# G772X.net
KiCad netlist of a schematic drawn in EAGLE
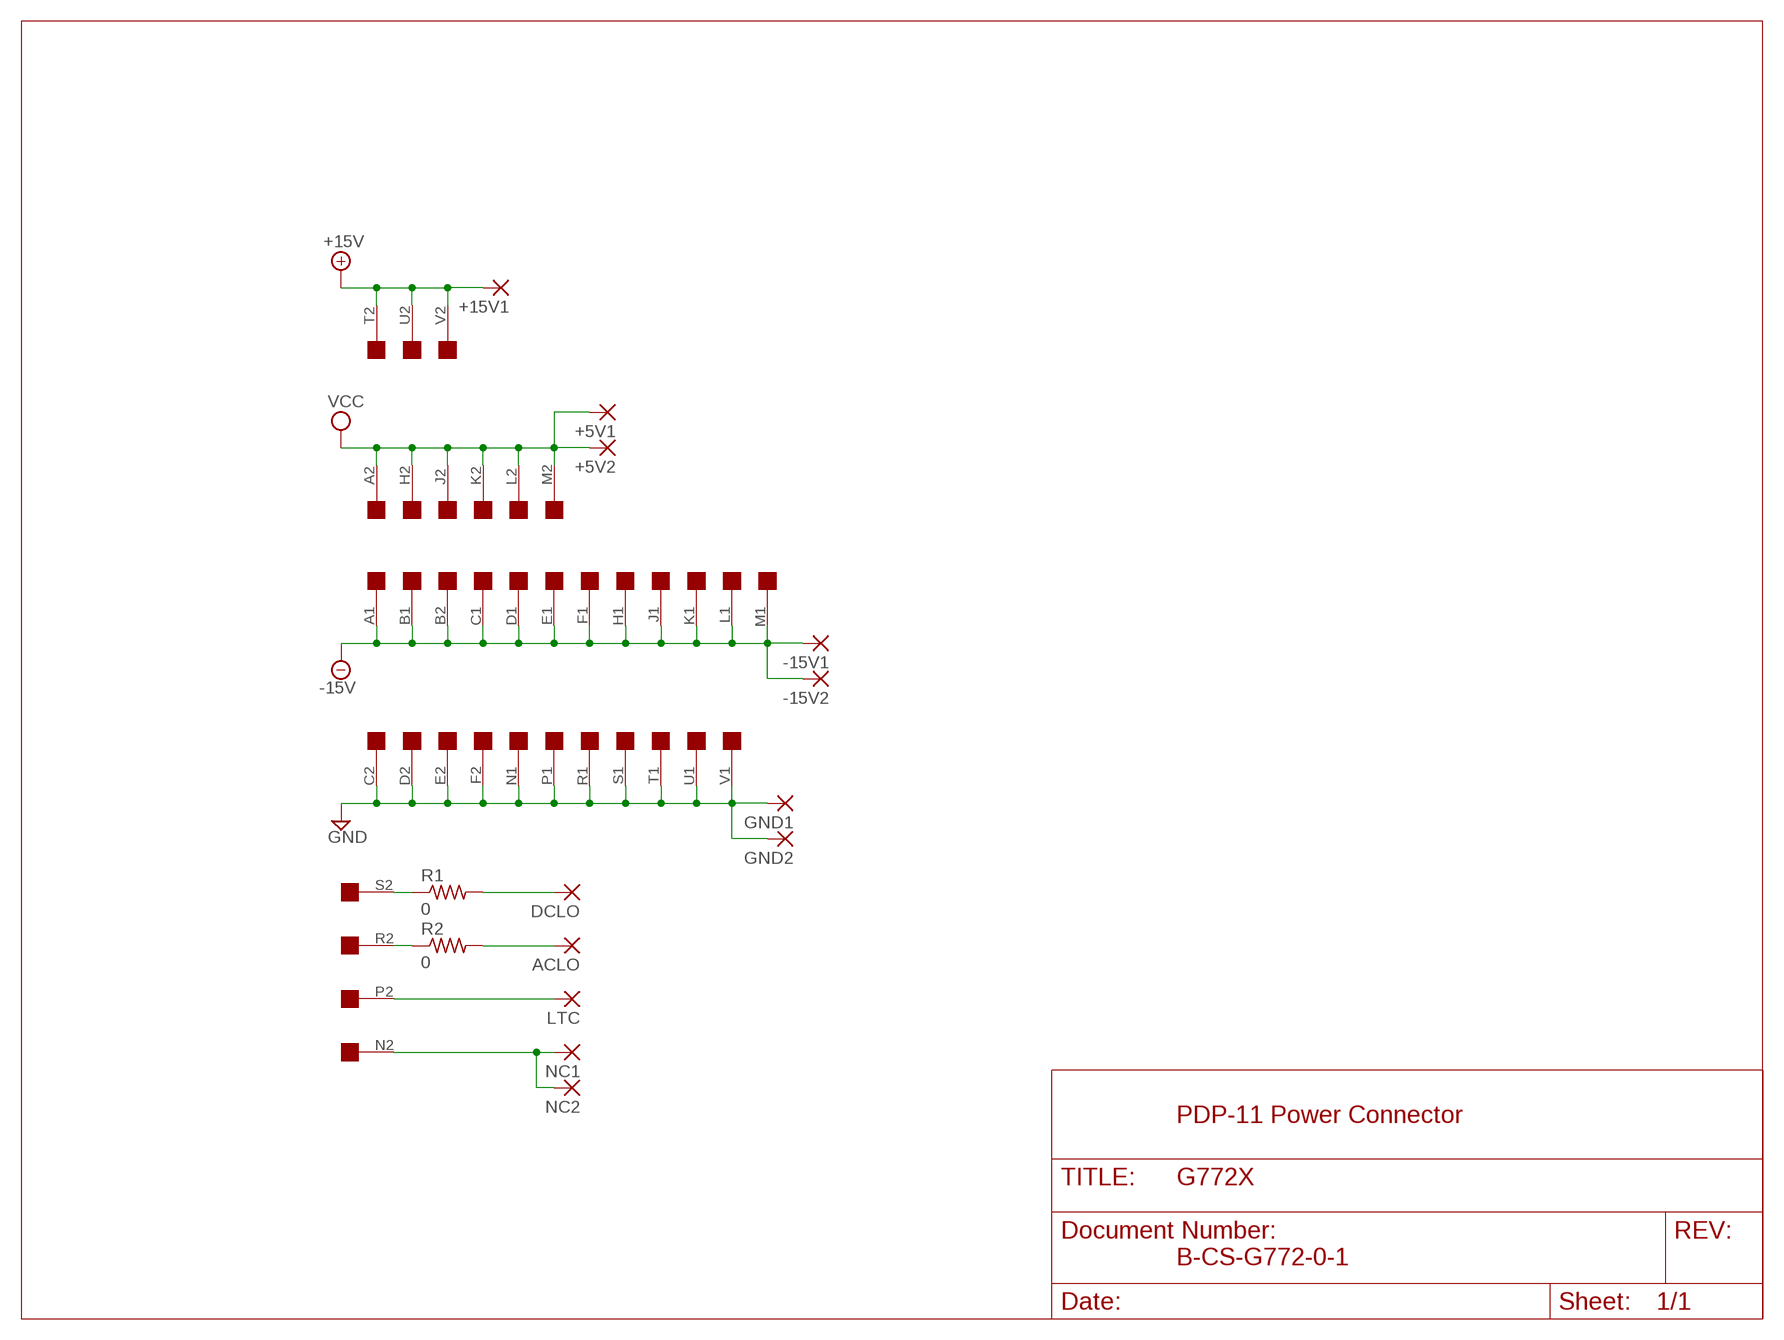
[diagram p0: schematic, sheet 1]

(export (version "E")
  (design (tool "Eeschema 10.0.6"))
  (components
    (comp (ref "+5V1")
      (value "2,54/1,0")
      (footprint "eagle-import:2,54_1,0")
      (libsource (lib "eagle-import") (part "2,54/1,0"))
    )
    (comp (ref "+5V2")
      (value "2,54/1,0")
      (footprint "eagle-import:2,54_1,0")
      (libsource (lib "eagle-import") (part "2,54/1,0"))
    )
    (comp (ref "+15V1")
      (value "2,54/1,0")
      (footprint "eagle-import:2,54_1,0")
      (libsource (lib "eagle-import") (part "2,54/1,0"))
    )
    (comp (ref "-15V1")
      (value "2,54/1,0")
      (footprint "eagle-import:2,54_1,0")
      (libsource (lib "eagle-import") (part "2,54/1,0"))
    )
    (comp (ref "-15V2")
      (value "2,54/1,0")
      (footprint "eagle-import:2,54_1,0")
      (libsource (lib "eagle-import") (part "2,54/1,0"))
    )
    (comp (ref "ACLO")
      (value "2,54/1,0")
      (footprint "eagle-import:2,54_1,0")
      (libsource (lib "eagle-import") (part "2,54/1,0"))
    )
    (comp (ref "DCLO")
      (value "2,54/1,0")
      (footprint "eagle-import:2,54_1,0")
      (libsource (lib "eagle-import") (part "2,54/1,0"))
    )
    (comp (ref "GND1")
      (value "2,54/1,0")
      (footprint "eagle-import:2,54_1,0")
      (libsource (lib "eagle-import") (part "2,54/1,0"))
    )
    (comp (ref "GND2")
      (value "2,54/1,0")
      (footprint "eagle-import:2,54_1,0")
      (libsource (lib "eagle-import") (part "2,54/1,0"))
    )
    (comp (ref "LTC")
      (value "2,54/1,0")
      (footprint "eagle-import:2,54_1,0")
      (libsource (lib "eagle-import") (part "2,54/1,0"))
    )
    (comp (ref "NC1")
      (value "2,54/1,0")
      (footprint "eagle-import:2,54_1,0")
      (libsource (lib "eagle-import") (part "2,54/1,0"))
    )
    (comp (ref "NC2")
      (value "2,54/1,0")
      (footprint "eagle-import:2,54_1,0")
      (libsource (lib "eagle-import") (part "2,54/1,0"))
    )
    (comp (ref "R1")
      (value "0")
      (footprint "eagle-import:0207_10")
      (libsource (lib "eagle-import") (part "R-US_0207/10"))
    )
    (comp (ref "R2")
      (value "0")
      (footprint "eagle-import:0207_10")
      (libsource (lib "eagle-import") (part "R-US_0207/10"))
    )
    (comp (ref "U$1")
      (value "SINGLE")
      (footprint "eagle-import:EDGE-CON2")
      (libsource (lib "eagle-import") (part "SINGLE"))
    )
  )
  (nets
    (net (code "1") (name "+15V") (class "Default")
      (node (ref "+15V1") (pin "1") (pinfunction "P_1") (pintype "passive"))
      (node (ref "U$1") (pin "T2") (pinfunction "1_T2") (pintype "bidirectional"))
      (node (ref "U$1") (pin "U2") (pinfunction "1_U2") (pintype "bidirectional"))
      (node (ref "U$1") (pin "V2") (pinfunction "1_V2") (pintype "bidirectional"))
    )
    (net (code "2") (name "-15V") (class "Default")
      (node (ref "-15V1") (pin "1") (pinfunction "P_1") (pintype "passive"))
      (node (ref "-15V2") (pin "1") (pinfunction "P_1") (pintype "passive"))
      (node (ref "U$1") (pin "A1") (pinfunction "1_A1") (pintype "bidirectional"))
      (node (ref "U$1") (pin "B1") (pinfunction "1_B1") (pintype "bidirectional"))
      (node (ref "U$1") (pin "B2") (pinfunction "1_B2") (pintype "bidirectional"))
      (node (ref "U$1") (pin "C1") (pinfunction "1_C1") (pintype "bidirectional"))
      (node (ref "U$1") (pin "D1") (pinfunction "1_D1") (pintype "bidirectional"))
      (node (ref "U$1") (pin "E1") (pinfunction "1_E1") (pintype "bidirectional"))
      (node (ref "U$1") (pin "F1") (pinfunction "1_F1") (pintype "bidirectional"))
      (node (ref "U$1") (pin "H1") (pinfunction "1_H1") (pintype "bidirectional"))
      (node (ref "U$1") (pin "J1") (pinfunction "1_J1") (pintype "bidirectional"))
      (node (ref "U$1") (pin "K1") (pinfunction "1_K1") (pintype "bidirectional"))
      (node (ref "U$1") (pin "L1") (pinfunction "1_L1") (pintype "bidirectional"))
      (node (ref "U$1") (pin "M1") (pinfunction "1_M1") (pintype "bidirectional"))
    )
    (net (code "3") (name "GND") (class "Default")
      (node (ref "GND1") (pin "1") (pinfunction "P_1") (pintype "passive"))
      (node (ref "GND2") (pin "1") (pinfunction "P_1") (pintype "passive"))
      (node (ref "U$1") (pin "C2") (pinfunction "1_C2") (pintype "bidirectional"))
      (node (ref "U$1") (pin "D2") (pinfunction "1_D2") (pintype "bidirectional"))
      (node (ref "U$1") (pin "E2") (pinfunction "1_E2") (pintype "bidirectional"))
      (node (ref "U$1") (pin "F2") (pinfunction "1_F2") (pintype "bidirectional"))
      (node (ref "U$1") (pin "N1") (pinfunction "1_N1") (pintype "bidirectional"))
      (node (ref "U$1") (pin "P1") (pinfunction "1_P1") (pintype "bidirectional"))
      (node (ref "U$1") (pin "R1") (pinfunction "1_R1") (pintype "bidirectional"))
      (node (ref "U$1") (pin "S1") (pinfunction "1_S1") (pintype "bidirectional"))
      (node (ref "U$1") (pin "T1") (pinfunction "1_T1") (pintype "bidirectional"))
      (node (ref "U$1") (pin "U1") (pinfunction "1_U1") (pintype "bidirectional"))
      (node (ref "U$1") (pin "V1") (pinfunction "1_V1") (pintype "bidirectional"))
    )
    (net (code "4") (name "Net-(ACLO-P)") (class "Default")
      (node (ref "ACLO") (pin "1") (pinfunction "P_1") (pintype "passive"))
      (node (ref "R2") (pin "2") (pinfunction "2_2") (pintype "passive"))
    )
    (net (code "5") (name "Net-(DCLO-P)") (class "Default")
      (node (ref "DCLO") (pin "1") (pinfunction "P_1") (pintype "passive"))
      (node (ref "R1") (pin "2") (pinfunction "2_2") (pintype "passive"))
    )
    (net (code "6") (name "Net-(LTC-P)") (class "Default")
      (node (ref "LTC") (pin "1") (pinfunction "P_1") (pintype "passive"))
      (node (ref "U$1") (pin "P2") (pinfunction "1_P2") (pintype "bidirectional"))
    )
    (net (code "7") (name "Net-(NC1-P)") (class "Default")
      (node (ref "NC1") (pin "1") (pinfunction "P_1") (pintype "passive"))
      (node (ref "NC2") (pin "1") (pinfunction "P_1") (pintype "passive"))
      (node (ref "U$1") (pin "N2") (pinfunction "1_N2") (pintype "bidirectional"))
    )
    (net (code "8") (name "Net-(U$1AB-1)") (class "Default")
      (node (ref "R2") (pin "1") (pinfunction "1_1") (pintype "passive"))
      (node (ref "U$1") (pin "R2") (pinfunction "1_R2") (pintype "bidirectional"))
    )
    (net (code "9") (name "Net-(U$1AD-1)") (class "Default")
      (node (ref "R1") (pin "1") (pinfunction "1_1") (pintype "passive"))
      (node (ref "U$1") (pin "S2") (pinfunction "1_S2") (pintype "bidirectional"))
    )
    (net (code "10") (name "VCC") (class "Default")
      (node (ref "+5V1") (pin "1") (pinfunction "P_1") (pintype "passive"))
      (node (ref "+5V2") (pin "1") (pinfunction "P_1") (pintype "passive"))
      (node (ref "U$1") (pin "A2") (pinfunction "1_A2") (pintype "bidirectional"))
      (node (ref "U$1") (pin "H2") (pinfunction "1_H2") (pintype "bidirectional"))
      (node (ref "U$1") (pin "J2") (pinfunction "1_J2") (pintype "bidirectional"))
      (node (ref "U$1") (pin "K2") (pinfunction "1_K2") (pintype "bidirectional"))
      (node (ref "U$1") (pin "L2") (pinfunction "1_L2") (pintype "bidirectional"))
      (node (ref "U$1") (pin "M2") (pinfunction "1_M2") (pintype "bidirectional"))
    )
  )
)
